# Oscillateur.net
KiCad netlist of a schematic drawn in Altium Designer
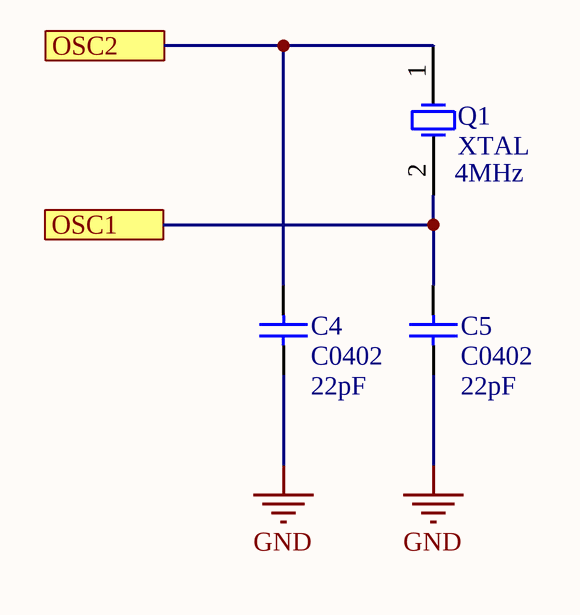
[diagram p0: Oscillateur.SchDoc]

(export (version "E")
  (design (tool "Eeschema 10.0.6"))
  (components
    (comp (ref "C4")
      (value "C0402")
      (footprint "0402")
      (description "Ceramic Chip Capacitor - Standard")
      (fields (field (name "ALTIUM_VALUE") "22pF") (field (name "PUBLISHER") "Altium Limited"))
      (libsource (lib "KEMET Chip Capacitor") (part "C0402"))
    )
    (comp (ref "C5")
      (value "C0402")
      (footprint "0402")
      (description "Ceramic Chip Capacitor - Standard")
      (fields (field (name "ALTIUM_VALUE") "22pF") (field (name "PUBLISHER") "Altium Limited"))
      (libsource (lib "KEMET Chip Capacitor") (part "C0402"))
    )
    (comp (ref "Q1")
      (value "XTAL")
      (footprint "R38")
      (description "Crystal Oscillator")
      (fields (field (name "ALTIUM_VALUE") "4MHz") (field (name "PUBLISHER") "Altium Limited"))
      (libsource (lib "Miscellaneous Devices") (part "XTAL"))
    )
  )
  (nets
    (net (code "1") (name "/OSC1") (class "Default")
      (node (ref "C5") (pin "2") (pinfunction "2_2") (pintype "passive"))
      (node (ref "Q1") (pin "2") (pinfunction "OSC2_2") (pintype "passive"))
    )
    (net (code "2") (name "/OSC2") (class "Default")
      (node (ref "C4") (pin "2") (pinfunction "2_2") (pintype "passive"))
      (node (ref "Q1") (pin "1") (pinfunction "OSC1_1") (pintype "passive"))
    )
    (net (code "3") (name "GND") (class "Default")
      (node (ref "C4") (pin "1") (pinfunction "1_1") (pintype "passive"))
      (node (ref "C5") (pin "1") (pinfunction "1_1") (pintype "passive"))
    )
  )
)
